# K64f_XFBGA_121_pin.net
KiCad netlist of a schematic drawn in Altium Designer
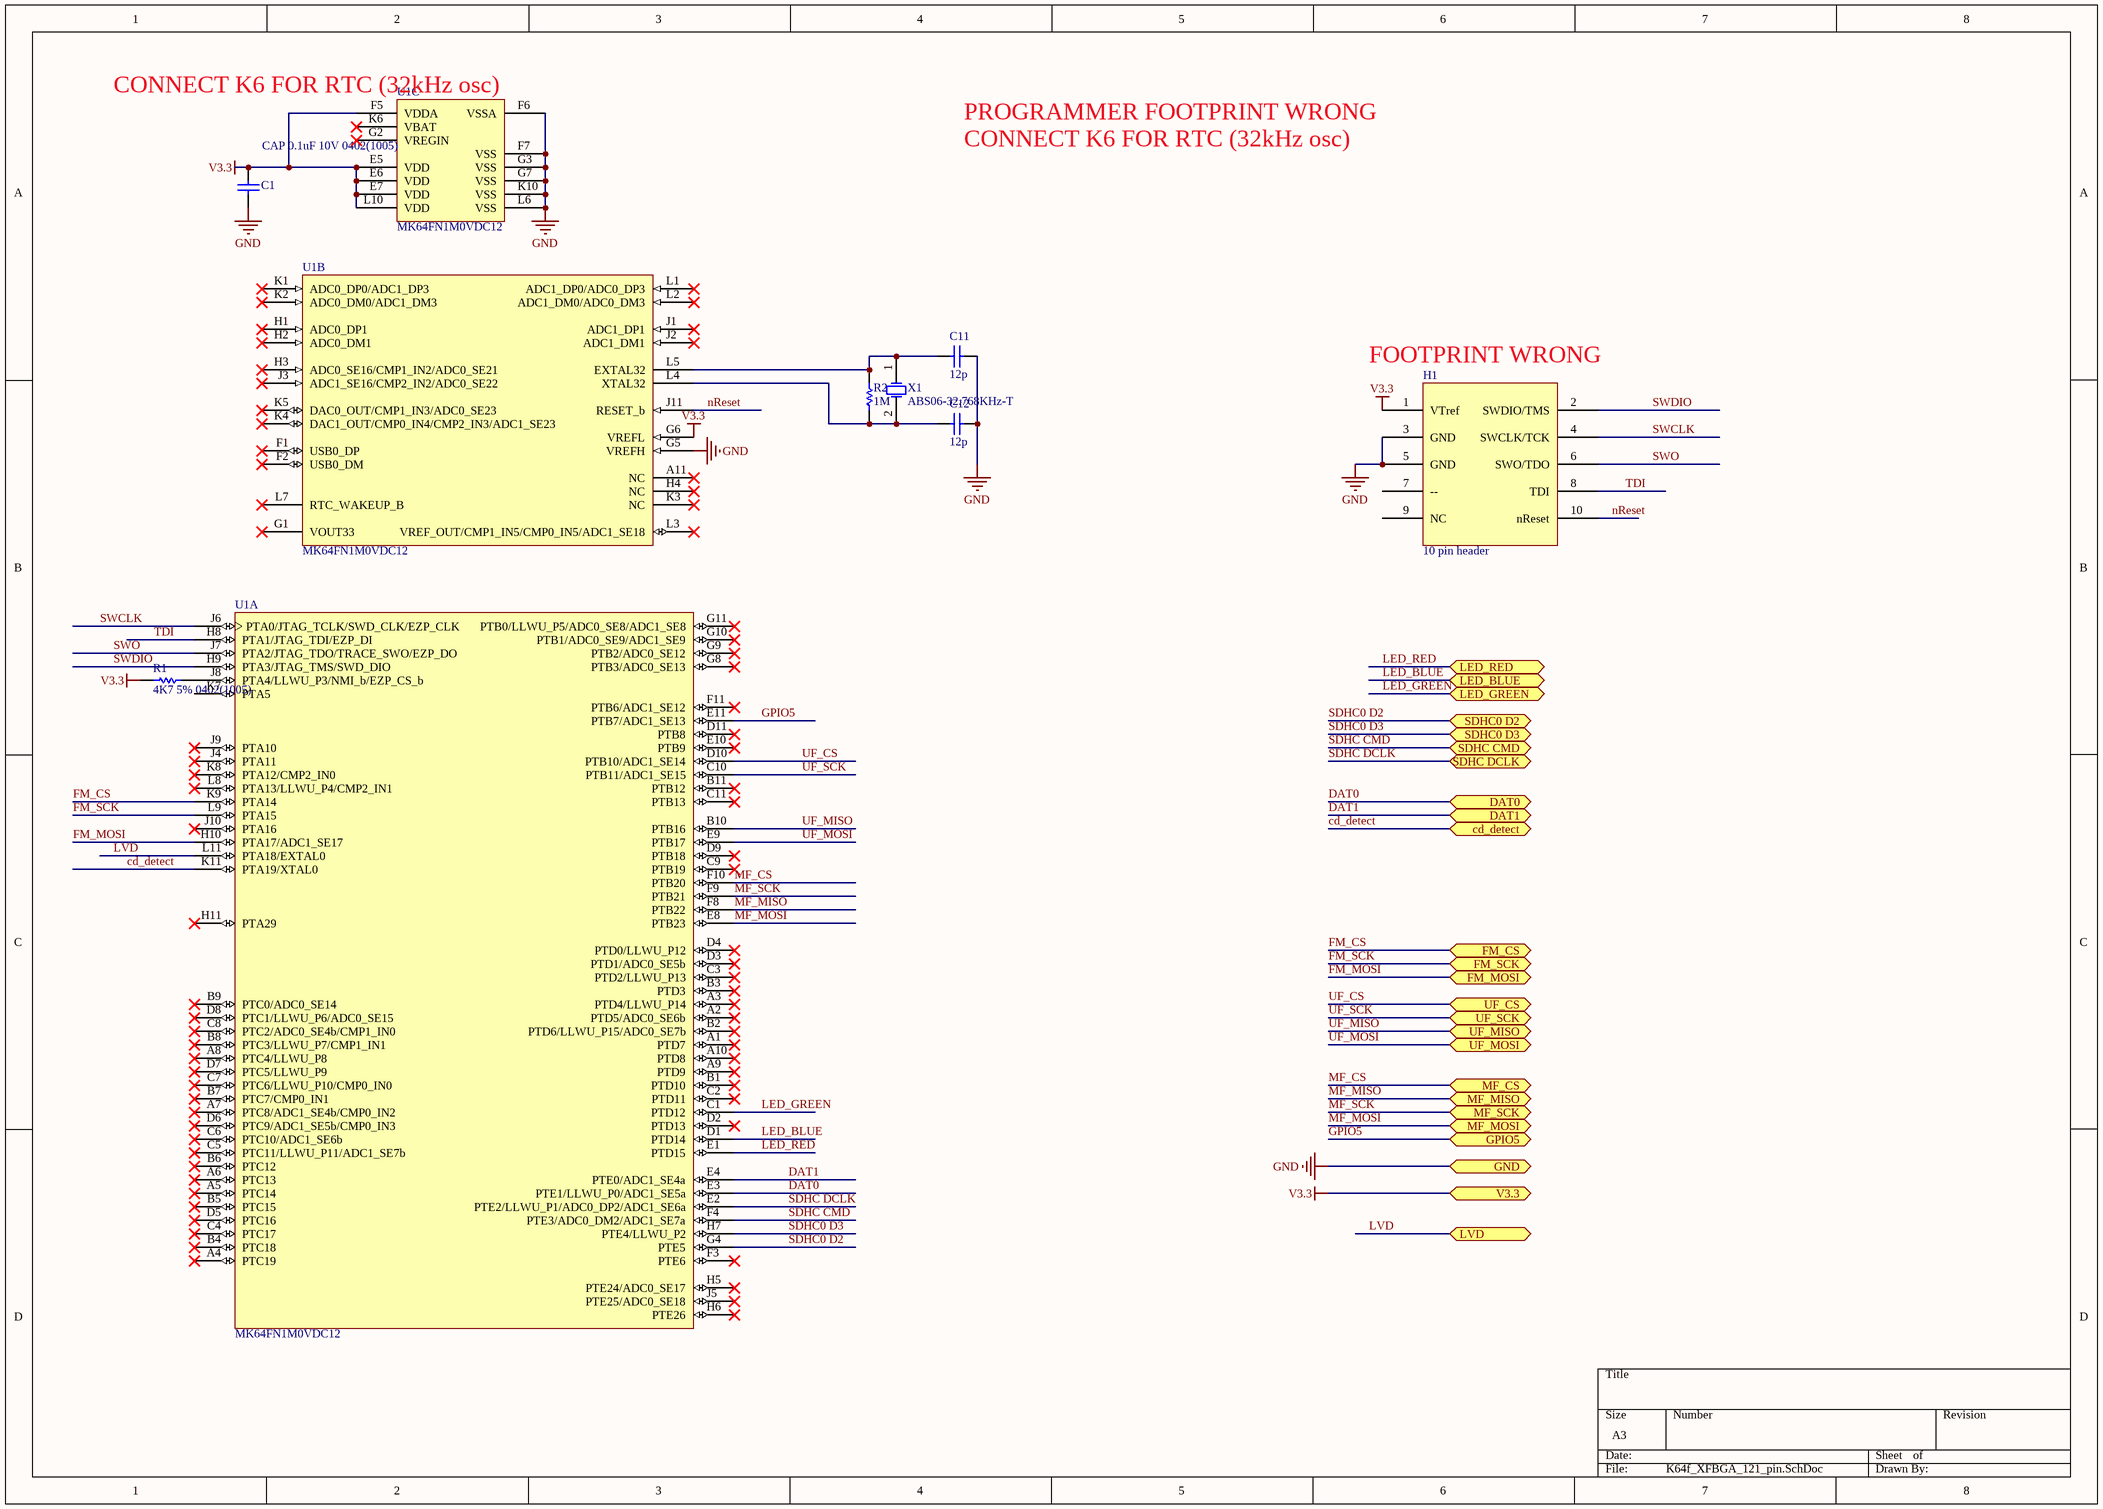
[diagram p0: K64f_XFBGA_121_pin.SchDoc]

(export (version "E")
  (design (tool "Eeschema 10.0.6"))
  (components
    (comp (ref "C1")
      (value "CAP 0.1uF 10V 0402(1005)")
      (footprint "CAPC0402(1005)60_M")
      (description "0.1uF")
      (fields (field (name "TOLERANCE") "Â±0.1pF"))
      (libsource (lib "Altium Content Vault") (part "CAP"))
    )
    (comp (ref "C11")
      (value "12p")
      (footprint "CAPC0402(1005)60_M")
      (description "CAP 12pF 10V ±0.1pF 0402 (1005 Metric) Thickness 0.6mm SMD")
      (fields (field (name "TOLERANCE") "Â±0.1pF"))
      (libsource (lib "Altium Content Vault") (part "CMP-1034-00013-1"))
    )
    (comp (ref "C12")
      (value "12p")
      (footprint "CAPC0402(1005)60_M")
      (description "CAP 12pF 10V ±0.1pF 0402 (1005 Metric) Thickness 0.6mm SMD")
      (fields (field (name "TOLERANCE") "Â±0.1pF"))
      (libsource (lib "Altium Content Vault") (part "CMP-1034-00013-1"))
    )
    (comp (ref "H1")
      (value "10 pin header")
      (footprint "SAM8795-ND")
      (description "10 pin programming header SAM8795-ND")
      (libsource (lib "Senseback_lib") (part "SAM8795-ND"))
    )
    (comp (ref "R1")
      (value "4K7 5% 0402(1005)")
      (footprint "RESC0402(1005)_L")
      (description "4K7 0.063W 5% 0402 (1005 Metric)  SMD")
      (fields (field (name "TOLERANCE") "5 %") (field (name "POWER") "0.063 W"))
      (libsource (lib "Altium Content Vault") (part "RES"))
    )
    (comp (ref "R2")
      (value "1M")
      (footprint "RESC0402(1005)_L")
      (description "1M 0.063W 5% 0402 (1005 Metric)  SMD")
      (fields (field (name "TOLERANCE") "5 %") (field (name "POWER") "0.063 W"))
      (libsource (lib "Altium Content Vault") (part "CMP-1011-00090-1"))
    )
    (comp (ref "U1")
      (value "MK64FN1M0VDC12")
      (footprint "FRES-MAPBGA-121")
      (fields (field (name "MANUFACTURER") "Freescale Semiconductor"))
      (libsource (lib "Altium Content Vault") (part "FRES-MK64FX512VDC12-121"))
    )
    (comp (ref "X1")
      (value "ABS06-32.768KHz-T")
      (footprint "0805")
      (description "Crystals 32.768KHz 20ppm 12.5pF -40C +85C 0805(2012)")
      (fields (field (name "PARTNUMBER") "14340272-32.768KHz") (field (name "MANUFACTURER") "ITTI"))
      (libsource (lib "altium-import") (part "root_3_ITTI-14340272-2_"))
    )
  )
  (nets
    (net (code "1") (name "/DAT0") (class "Default")
      (node (ref "U1") (pin "E3") (pinfunction "PTE1/LLWU_P0/ADC1_SE5a_E3") (pintype "bidirectional"))
    )
    (net (code "2") (name "/DAT1") (class "Default")
      (node (ref "U1") (pin "E4") (pinfunction "PTE0/ADC1_SE4a_E4") (pintype "bidirectional"))
    )
    (net (code "3") (name "/FM_CS") (class "Default")
      (node (ref "U1") (pin "K9") (pinfunction "PTA14_K9") (pintype "bidirectional"))
    )
    (net (code "4") (name "/FM_MOSI") (class "Default")
      (node (ref "U1") (pin "H10") (pinfunction "PTA17/ADC1_SE17_H10") (pintype "bidirectional"))
    )
    (net (code "5") (name "/FM_SCK") (class "Default")
      (node (ref "U1") (pin "L9") (pinfunction "PTA15_L9") (pintype "bidirectional"))
    )
    (net (code "6") (name "/GPIO5") (class "Default")
      (node (ref "U1") (pin "E11") (pinfunction "PTB7/ADC1_SE13_E11") (pintype "bidirectional"))
    )
    (net (code "7") (name "/LED_BLUE") (class "Default")
      (node (ref "U1") (pin "D1") (pinfunction "PTD14_D1") (pintype "bidirectional"))
    )
    (net (code "8") (name "/LED_GREEN") (class "Default")
      (node (ref "U1") (pin "C1") (pinfunction "PTD12_C1") (pintype "bidirectional"))
    )
    (net (code "9") (name "/LED_RED") (class "Default")
      (node (ref "U1") (pin "E1") (pinfunction "PTD15_E1") (pintype "bidirectional"))
    )
    (net (code "10") (name "/LVD") (class "Default")
      (node (ref "U1") (pin "L11") (pinfunction "PTA18/EXTAL0_L11") (pintype "bidirectional"))
    )
    (net (code "11") (name "/MF_CS") (class "Default")
      (node (ref "U1") (pin "F10") (pinfunction "PTB20_F10") (pintype "bidirectional"))
    )
    (net (code "12") (name "/MF_MISO") (class "Default")
      (node (ref "U1") (pin "F8") (pinfunction "PTB22_F8") (pintype "bidirectional"))
    )
    (net (code "13") (name "/MF_MOSI") (class "Default")
      (node (ref "U1") (pin "E8") (pinfunction "PTB23_E8") (pintype "bidirectional"))
    )
    (net (code "14") (name "/MF_SCK") (class "Default")
      (node (ref "U1") (pin "F9") (pinfunction "PTB21_F9") (pintype "bidirectional"))
    )
    (net (code "15") (name "/SDHC CMD") (class "Default")
      (node (ref "U1") (pin "F4") (pinfunction "PTE3/ADC0_DM2/ADC1_SE7a_F4") (pintype "bidirectional"))
    )
    (net (code "16") (name "/SDHC DCLK") (class "Default")
      (node (ref "U1") (pin "E2") (pinfunction "PTE2/LLWU_P1/ADC0_DP2/ADC1_SE6a_E2") (pintype "bidirectional"))
    )
    (net (code "17") (name "/SDHC0 D2") (class "Default")
      (node (ref "U1") (pin "G4") (pinfunction "PTE5_G4") (pintype "bidirectional"))
    )
    (net (code "18") (name "/SDHC0 D3") (class "Default")
      (node (ref "U1") (pin "H7") (pinfunction "PTE4/LLWU_P2_H7") (pintype "bidirectional"))
    )
    (net (code "19") (name "/SWCLK") (class "Default")
      (node (ref "H1") (pin "4") (pinfunction "SWCLK/TCK_4") (pintype "passive"))
      (node (ref "U1") (pin "J6") (pinfunction "PTA0/JTAG_TCLK/SWD_CLK/EZP_CLK_J6") (pintype "bidirectional"))
    )
    (net (code "20") (name "/SWDIO") (class "Default")
      (node (ref "H1") (pin "2") (pinfunction "SWDIO/TMS_2") (pintype "passive"))
      (node (ref "U1") (pin "H9") (pinfunction "PTA3/JTAG_TMS/SWD_DIO_H9") (pintype "bidirectional"))
    )
    (net (code "21") (name "/SWO") (class "Default")
      (node (ref "H1") (pin "6") (pinfunction "SWO/TDO_6") (pintype "passive"))
      (node (ref "U1") (pin "J7") (pinfunction "PTA2/JTAG_TDO/TRACE_SWO/EZP_DO_J7") (pintype "bidirectional"))
    )
    (net (code "22") (name "/TDI") (class "Default")
      (node (ref "H1") (pin "8") (pinfunction "TDI_8") (pintype "passive"))
      (node (ref "U1") (pin "H8") (pinfunction "PTA1/JTAG_TDI/EZP_DI_H8") (pintype "bidirectional"))
    )
    (net (code "23") (name "/UF_CS") (class "Default")
      (node (ref "U1") (pin "D10") (pinfunction "PTB10/ADC1_SE14_D10") (pintype "bidirectional"))
    )
    (net (code "24") (name "/UF_MISO") (class "Default")
      (node (ref "U1") (pin "B10") (pinfunction "PTB16_B10") (pintype "bidirectional"))
    )
    (net (code "25") (name "/UF_MOSI") (class "Default")
      (node (ref "U1") (pin "E9") (pinfunction "PTB17_E9") (pintype "bidirectional"))
    )
    (net (code "26") (name "/UF_SCK") (class "Default")
      (node (ref "U1") (pin "C10") (pinfunction "PTB11/ADC1_SE15_C10") (pintype "bidirectional"))
    )
    (net (code "27") (name "/cd_detect") (class "Default")
      (node (ref "U1") (pin "K11") (pinfunction "PTA19/XTAL0_K11") (pintype "bidirectional"))
    )
    (net (code "28") (name "/nReset") (class "Default")
      (node (ref "H1") (pin "10") (pinfunction "nReset_10") (pintype "passive"))
      (node (ref "U1") (pin "J11") (pinfunction "RESET_b_J11") (pintype "input"))
    )
    (net (code "29") (name "GND") (class "Default")
      (node (ref "C1") (pin "1") (pinfunction "1_1") (pintype "passive"))
      (node (ref "C11") (pin "1") (pinfunction "1_1") (pintype "passive"))
      (node (ref "C12") (pin "1") (pinfunction "1_1") (pintype "passive"))
      (node (ref "H1") (pin "3") (pinfunction "GND_3") (pintype "passive"))
      (node (ref "H1") (pin "5") (pinfunction "GND_5") (pintype "passive"))
      (node (ref "U1") (pin "F6") (pinfunction "VSSA_F6") (pintype "power_in"))
      (node (ref "U1") (pin "F7") (pinfunction "VSS_F7") (pintype "power_in"))
      (node (ref "U1") (pin "G3") (pinfunction "VSS_G3") (pintype "power_in"))
      (node (ref "U1") (pin "G5") (pinfunction "VREFH_G5") (pintype "input"))
      (node (ref "U1") (pin "G7") (pinfunction "VSS_G7") (pintype "power_in"))
      (node (ref "U1") (pin "K10") (pinfunction "VSS_K10") (pintype "power_in"))
      (node (ref "U1") (pin "L6") (pinfunction "VSS_L6") (pintype "power_in"))
    )
    (net (code "30") (name "Net-(U1A-PTA4{slash}LLWU_P3{slash}NMI_b{slash}EZP_CS_b)") (class "Default")
      (node (ref "R1") (pin "2") (pinfunction "2_2") (pintype "passive"))
      (node (ref "U1") (pin "J8") (pinfunction "PTA4/LLWU_P3/NMI_b/EZP_CS_b_J8") (pintype "bidirectional"))
    )
    (net (code "31") (name "Net-(U1B-EXTAL32)") (class "Default")
      (node (ref "C11") (pin "2") (pinfunction "2_2") (pintype "passive"))
      (node (ref "R2") (pin "1") (pinfunction "1_1") (pintype "passive"))
      (node (ref "U1") (pin "L5") (pinfunction "EXTAL32_L5") (pintype "passive"))
      (node (ref "X1") (pin "1") (pinfunction "X1_1") (pintype "passive"))
    )
    (net (code "32") (name "Net-(U1B-XTAL32)") (class "Default")
      (node (ref "C12") (pin "2") (pinfunction "2_2") (pintype "passive"))
      (node (ref "R2") (pin "2") (pinfunction "2_2") (pintype "passive"))
      (node (ref "U1") (pin "L4") (pinfunction "XTAL32_L4") (pintype "passive"))
      (node (ref "X1") (pin "2") (pinfunction "X2_2") (pintype "passive"))
    )
    (net (code "33") (name "V3.3") (class "Default")
      (node (ref "C1") (pin "2") (pinfunction "2_2") (pintype "passive"))
      (node (ref "H1") (pin "1") (pinfunction "VTref_1") (pintype "passive"))
      (node (ref "R1") (pin "1") (pinfunction "1_1") (pintype "passive"))
      (node (ref "U1") (pin "E5") (pinfunction "VDD_E5") (pintype "power_in"))
      (node (ref "U1") (pin "E6") (pinfunction "VDD_E6") (pintype "power_in"))
      (node (ref "U1") (pin "E7") (pinfunction "VDD_E7") (pintype "power_in"))
      (node (ref "U1") (pin "F5") (pinfunction "VDDA_F5") (pintype "power_in"))
      (node (ref "U1") (pin "G6") (pinfunction "VREFL_G6") (pintype "input"))
      (node (ref "U1") (pin "L10") (pinfunction "VDD_L10") (pintype "power_in"))
    )
    (net (code "34") (name "unconnected-(H1----Pad7)") (class "Default")
      (node (ref "H1") (pin "7") (pinfunction "--_7") (pintype "passive"))
    )
    (net (code "35") (name "unconnected-(H1-NC-Pad9)") (class "Default")
      (node (ref "H1") (pin "9") (pinfunction "NC_9") (pintype "passive"))
    )
    (net (code "36") (name "unconnected-(U1A-PTA5-PadK7)") (class "Default")
      (node (ref "U1") (pin "K7") (pinfunction "PTA5_K7") (pintype "bidirectional"))
    )
    (net (code "37") (name "unconnected-(U1A-PTA10-PadJ9)") (class "Default")
      (node (ref "U1") (pin "J9") (pinfunction "PTA10_J9") (pintype "bidirectional+no_connect"))
    )
    (net (code "38") (name "unconnected-(U1A-PTA11-PadJ4)") (class "Default")
      (node (ref "U1") (pin "J4") (pinfunction "PTA11_J4") (pintype "bidirectional+no_connect"))
    )
    (net (code "39") (name "unconnected-(U1A-PTA12{slash}CMP2_IN0-PadK8)") (class "Default")
      (node (ref "U1") (pin "K8") (pinfunction "PTA12/CMP2_IN0_K8") (pintype "bidirectional+no_connect"))
    )
    (net (code "40") (name "unconnected-(U1A-PTA13{slash}LLWU_P4{slash}CMP2_IN1-PadL8)") (class "Default")
      (node (ref "U1") (pin "L8") (pinfunction "PTA13/LLWU_P4/CMP2_IN1_L8") (pintype "bidirectional+no_connect"))
    )
    (net (code "41") (name "unconnected-(U1A-PTA16-PadJ10)") (class "Default")
      (node (ref "U1") (pin "J10") (pinfunction "PTA16_J10") (pintype "bidirectional+no_connect"))
    )
    (net (code "42") (name "unconnected-(U1A-PTA29-PadH11)") (class "Default")
      (node (ref "U1") (pin "H11") (pinfunction "PTA29_H11") (pintype "bidirectional+no_connect"))
    )
    (net (code "43") (name "unconnected-(U1A-PTB0{slash}LLWU_P5{slash}ADC0_SE8{slash}ADC1_SE8-PadG11)") (class "Default")
      (node (ref "U1") (pin "G11") (pinfunction "PTB0/LLWU_P5/ADC0_SE8/ADC1_SE8_G11") (pintype "bidirectional+no_connect"))
    )
    (net (code "44") (name "unconnected-(U1A-PTB1{slash}ADC0_SE9{slash}ADC1_SE9-PadG10)") (class "Default")
      (node (ref "U1") (pin "G10") (pinfunction "PTB1/ADC0_SE9/ADC1_SE9_G10") (pintype "bidirectional+no_connect"))
    )
    (net (code "45") (name "unconnected-(U1A-PTB2{slash}ADC0_SE12-PadG9)") (class "Default")
      (node (ref "U1") (pin "G9") (pinfunction "PTB2/ADC0_SE12_G9") (pintype "bidirectional+no_connect"))
    )
    (net (code "46") (name "unconnected-(U1A-PTB3{slash}ADC0_SE13-PadG8)") (class "Default")
      (node (ref "U1") (pin "G8") (pinfunction "PTB3/ADC0_SE13_G8") (pintype "bidirectional+no_connect"))
    )
    (net (code "47") (name "unconnected-(U1A-PTB6{slash}ADC1_SE12-PadF11)") (class "Default")
      (node (ref "U1") (pin "F11") (pinfunction "PTB6/ADC1_SE12_F11") (pintype "bidirectional+no_connect"))
    )
    (net (code "48") (name "unconnected-(U1A-PTB8-PadD11)") (class "Default")
      (node (ref "U1") (pin "D11") (pinfunction "PTB8_D11") (pintype "bidirectional+no_connect"))
    )
    (net (code "49") (name "unconnected-(U1A-PTB9-PadE10)") (class "Default")
      (node (ref "U1") (pin "E10") (pinfunction "PTB9_E10") (pintype "bidirectional+no_connect"))
    )
    (net (code "50") (name "unconnected-(U1A-PTB12-PadB11)") (class "Default")
      (node (ref "U1") (pin "B11") (pinfunction "PTB12_B11") (pintype "bidirectional+no_connect"))
    )
    (net (code "51") (name "unconnected-(U1A-PTB13-PadC11)") (class "Default")
      (node (ref "U1") (pin "C11") (pinfunction "PTB13_C11") (pintype "bidirectional+no_connect"))
    )
    (net (code "52") (name "unconnected-(U1A-PTB18-PadD9)") (class "Default")
      (node (ref "U1") (pin "D9") (pinfunction "PTB18_D9") (pintype "bidirectional+no_connect"))
    )
    (net (code "53") (name "unconnected-(U1A-PTB19-PadC9)") (class "Default")
      (node (ref "U1") (pin "C9") (pinfunction "PTB19_C9") (pintype "bidirectional+no_connect"))
    )
    (net (code "54") (name "unconnected-(U1A-PTC0{slash}ADC0_SE14-PadB9)") (class "Default")
      (node (ref "U1") (pin "B9") (pinfunction "PTC0/ADC0_SE14_B9") (pintype "bidirectional+no_connect"))
    )
    (net (code "55") (name "unconnected-(U1A-PTC1{slash}LLWU_P6{slash}ADC0_SE15-PadD8)") (class "Default")
      (node (ref "U1") (pin "D8") (pinfunction "PTC1/LLWU_P6/ADC0_SE15_D8") (pintype "bidirectional+no_connect"))
    )
    (net (code "56") (name "unconnected-(U1A-PTC2{slash}ADC0_SE4b{slash}CMP1_IN0-PadC8)") (class "Default")
      (node (ref "U1") (pin "C8") (pinfunction "PTC2/ADC0_SE4b/CMP1_IN0_C8") (pintype "bidirectional+no_connect"))
    )
    (net (code "57") (name "unconnected-(U1A-PTC3{slash}LLWU_P7{slash}CMP1_IN1-PadB8)") (class "Default")
      (node (ref "U1") (pin "B8") (pinfunction "PTC3/LLWU_P7/CMP1_IN1_B8") (pintype "bidirectional+no_connect"))
    )
    (net (code "58") (name "unconnected-(U1A-PTC4{slash}LLWU_P8-PadA8)") (class "Default")
      (node (ref "U1") (pin "A8") (pinfunction "PTC4/LLWU_P8_A8") (pintype "bidirectional+no_connect"))
    )
    (net (code "59") (name "unconnected-(U1A-PTC5{slash}LLWU_P9-PadD7)") (class "Default")
      (node (ref "U1") (pin "D7") (pinfunction "PTC5/LLWU_P9_D7") (pintype "bidirectional+no_connect"))
    )
    (net (code "60") (name "unconnected-(U1A-PTC6{slash}LLWU_P10{slash}CMP0_IN0-PadC7)") (class "Default")
      (node (ref "U1") (pin "C7") (pinfunction "PTC6/LLWU_P10/CMP0_IN0_C7") (pintype "bidirectional+no_connect"))
    )
    (net (code "61") (name "unconnected-(U1A-PTC7{slash}CMP0_IN1-PadB7)") (class "Default")
      (node (ref "U1") (pin "B7") (pinfunction "PTC7/CMP0_IN1_B7") (pintype "bidirectional+no_connect"))
    )
    (net (code "62") (name "unconnected-(U1A-PTC8{slash}ADC1_SE4b{slash}CMP0_IN2-PadA7)") (class "Default")
      (node (ref "U1") (pin "A7") (pinfunction "PTC8/ADC1_SE4b/CMP0_IN2_A7") (pintype "bidirectional+no_connect"))
    )
    (net (code "63") (name "unconnected-(U1A-PTC9{slash}ADC1_SE5b{slash}CMP0_IN3-PadD6)") (class "Default")
      (node (ref "U1") (pin "D6") (pinfunction "PTC9/ADC1_SE5b/CMP0_IN3_D6") (pintype "bidirectional+no_connect"))
    )
    (net (code "64") (name "unconnected-(U1A-PTC10{slash}ADC1_SE6b-PadC6)") (class "Default")
      (node (ref "U1") (pin "C6") (pinfunction "PTC10/ADC1_SE6b_C6") (pintype "bidirectional+no_connect"))
    )
    (net (code "65") (name "unconnected-(U1A-PTC11{slash}LLWU_P11{slash}ADC1_SE7b-PadC5)") (class "Default")
      (node (ref "U1") (pin "C5") (pinfunction "PTC11/LLWU_P11/ADC1_SE7b_C5") (pintype "bidirectional+no_connect"))
    )
    (net (code "66") (name "unconnected-(U1A-PTC12-PadB6)") (class "Default")
      (node (ref "U1") (pin "B6") (pinfunction "PTC12_B6") (pintype "bidirectional+no_connect"))
    )
    (net (code "67") (name "unconnected-(U1A-PTC13-PadA6)") (class "Default")
      (node (ref "U1") (pin "A6") (pinfunction "PTC13_A6") (pintype "bidirectional+no_connect"))
    )
    (net (code "68") (name "unconnected-(U1A-PTC14-PadA5)") (class "Default")
      (node (ref "U1") (pin "A5") (pinfunction "PTC14_A5") (pintype "bidirectional+no_connect"))
    )
    (net (code "69") (name "unconnected-(U1A-PTC15-PadB5)") (class "Default")
      (node (ref "U1") (pin "B5") (pinfunction "PTC15_B5") (pintype "bidirectional+no_connect"))
    )
    (net (code "70") (name "unconnected-(U1A-PTC16-PadD5)") (class "Default")
      (node (ref "U1") (pin "D5") (pinfunction "PTC16_D5") (pintype "bidirectional+no_connect"))
    )
    (net (code "71") (name "unconnected-(U1A-PTC17-PadC4)") (class "Default")
      (node (ref "U1") (pin "C4") (pinfunction "PTC17_C4") (pintype "bidirectional+no_connect"))
    )
    (net (code "72") (name "unconnected-(U1A-PTC18-PadB4)") (class "Default")
      (node (ref "U1") (pin "B4") (pinfunction "PTC18_B4") (pintype "bidirectional+no_connect"))
    )
    (net (code "73") (name "unconnected-(U1A-PTC19-PadA4)") (class "Default")
      (node (ref "U1") (pin "A4") (pinfunction "PTC19_A4") (pintype "bidirectional+no_connect"))
    )
    (net (code "74") (name "unconnected-(U1A-PTD0{slash}LLWU_P12-PadD4)") (class "Default")
      (node (ref "U1") (pin "D4") (pinfunction "PTD0/LLWU_P12_D4") (pintype "bidirectional+no_connect"))
    )
    (net (code "75") (name "unconnected-(U1A-PTD1{slash}ADC0_SE5b-PadD3)") (class "Default")
      (node (ref "U1") (pin "D3") (pinfunction "PTD1/ADC0_SE5b_D3") (pintype "bidirectional+no_connect"))
    )
    (net (code "76") (name "unconnected-(U1A-PTD2{slash}LLWU_P13-PadC3)") (class "Default")
      (node (ref "U1") (pin "C3") (pinfunction "PTD2/LLWU_P13_C3") (pintype "bidirectional+no_connect"))
    )
    (net (code "77") (name "unconnected-(U1A-PTD3-PadB3)") (class "Default")
      (node (ref "U1") (pin "B3") (pinfunction "PTD3_B3") (pintype "bidirectional+no_connect"))
    )
    (net (code "78") (name "unconnected-(U1A-PTD4{slash}LLWU_P14-PadA3)") (class "Default")
      (node (ref "U1") (pin "A3") (pinfunction "PTD4/LLWU_P14_A3") (pintype "bidirectional+no_connect"))
    )
    (net (code "79") (name "unconnected-(U1A-PTD5{slash}ADC0_SE6b-PadA2)") (class "Default")
      (node (ref "U1") (pin "A2") (pinfunction "PTD5/ADC0_SE6b_A2") (pintype "bidirectional+no_connect"))
    )
    (net (code "80") (name "unconnected-(U1A-PTD6{slash}LLWU_P15{slash}ADC0_SE7b-PadB2)") (class "Default")
      (node (ref "U1") (pin "B2") (pinfunction "PTD6/LLWU_P15/ADC0_SE7b_B2") (pintype "bidirectional+no_connect"))
    )
    (net (code "81") (name "unconnected-(U1A-PTD7-PadA1)") (class "Default")
      (node (ref "U1") (pin "A1") (pinfunction "PTD7_A1") (pintype "bidirectional+no_connect"))
    )
    (net (code "82") (name "unconnected-(U1A-PTD8-PadA10)") (class "Default")
      (node (ref "U1") (pin "A10") (pinfunction "PTD8_A10") (pintype "bidirectional+no_connect"))
    )
    (net (code "83") (name "unconnected-(U1A-PTD9-PadA9)") (class "Default")
      (node (ref "U1") (pin "A9") (pinfunction "PTD9_A9") (pintype "bidirectional+no_connect"))
    )
    (net (code "84") (name "unconnected-(U1A-PTD10-PadB1)") (class "Default")
      (node (ref "U1") (pin "B1") (pinfunction "PTD10_B1") (pintype "bidirectional+no_connect"))
    )
    (net (code "85") (name "unconnected-(U1A-PTD11-PadC2)") (class "Default")
      (node (ref "U1") (pin "C2") (pinfunction "PTD11_C2") (pintype "bidirectional+no_connect"))
    )
    (net (code "86") (name "unconnected-(U1A-PTD13-PadD2)") (class "Default")
      (node (ref "U1") (pin "D2") (pinfunction "PTD13_D2") (pintype "bidirectional+no_connect"))
    )
    (net (code "87") (name "unconnected-(U1A-PTE6-PadF3)") (class "Default")
      (node (ref "U1") (pin "F3") (pinfunction "PTE6_F3") (pintype "bidirectional+no_connect"))
    )
    (net (code "88") (name "unconnected-(U1A-PTE24{slash}ADC0_SE17-PadH5)") (class "Default")
      (node (ref "U1") (pin "H5") (pinfunction "PTE24/ADC0_SE17_H5") (pintype "bidirectional+no_connect"))
    )
    (net (code "89") (name "unconnected-(U1A-PTE25{slash}ADC0_SE18-PadJ5)") (class "Default")
      (node (ref "U1") (pin "J5") (pinfunction "PTE25/ADC0_SE18_J5") (pintype "bidirectional+no_connect"))
    )
    (net (code "90") (name "unconnected-(U1A-PTE26-PadH6)") (class "Default")
      (node (ref "U1") (pin "H6") (pinfunction "PTE26_H6") (pintype "bidirectional+no_connect"))
    )
    (net (code "91") (name "unconnected-(U1B-ADC0_DM0{slash}ADC1_DM3-PadK2)") (class "Default")
      (node (ref "U1") (pin "K2") (pinfunction "ADC0_DM0/ADC1_DM3_K2") (pintype "input+no_connect"))
    )
    (net (code "92") (name "unconnected-(U1B-ADC0_DM1-PadH2)") (class "Default")
      (node (ref "U1") (pin "H2") (pinfunction "ADC0_DM1_H2") (pintype "input+no_connect"))
    )
    (net (code "93") (name "unconnected-(U1B-ADC0_DP0{slash}ADC1_DP3-PadK1)") (class "Default")
      (node (ref "U1") (pin "K1") (pinfunction "ADC0_DP0/ADC1_DP3_K1") (pintype "input+no_connect"))
    )
    (net (code "94") (name "unconnected-(U1B-ADC0_DP1-PadH1)") (class "Default")
      (node (ref "U1") (pin "H1") (pinfunction "ADC0_DP1_H1") (pintype "input+no_connect"))
    )
    (net (code "95") (name "unconnected-(U1B-ADC0_SE16{slash}CMP1_IN2{slash}ADC0_SE21-PadH3)") (class "Default")
      (node (ref "U1") (pin "H3") (pinfunction "ADC0_SE16/CMP1_IN2/ADC0_SE21_H3") (pintype "input+no_connect"))
    )
    (net (code "96") (name "unconnected-(U1B-ADC1_DM0{slash}ADC0_DM3-PadL2)") (class "Default")
      (node (ref "U1") (pin "L2") (pinfunction "ADC1_DM0/ADC0_DM3_L2") (pintype "input+no_connect"))
    )
    (net (code "97") (name "unconnected-(U1B-ADC1_DM1-PadJ2)") (class "Default")
      (node (ref "U1") (pin "J2") (pinfunction "ADC1_DM1_J2") (pintype "input+no_connect"))
    )
    (net (code "98") (name "unconnected-(U1B-ADC1_DP0{slash}ADC0_DP3-PadL1)") (class "Default")
      (node (ref "U1") (pin "L1") (pinfunction "ADC1_DP0/ADC0_DP3_L1") (pintype "input+no_connect"))
    )
    (net (code "99") (name "unconnected-(U1B-ADC1_DP1-PadJ1)") (class "Default")
      (node (ref "U1") (pin "J1") (pinfunction "ADC1_DP1_J1") (pintype "input+no_connect"))
    )
    (net (code "100") (name "unconnected-(U1B-ADC1_SE16{slash}CMP2_IN2{slash}ADC0_SE22-PadJ3)") (class "Default")
      (node (ref "U1") (pin "J3") (pinfunction "ADC1_SE16/CMP2_IN2/ADC0_SE22_J3") (pintype "input+no_connect"))
    )
    (net (code "101") (name "unconnected-(U1B-DAC0_OUT{slash}CMP1_IN3{slash}ADC0_SE23-PadK5)") (class "Default")
      (node (ref "U1") (pin "K5") (pinfunction "DAC0_OUT/CMP1_IN3/ADC0_SE23_K5") (pintype "bidirectional+no_connect"))
    )
    (net (code "102") (name "unconnected-(U1B-DAC1_OUT{slash}CMP0_IN4{slash}CMP2_IN3{slash}ADC1_SE23-PadK4)") (class "Default")
      (node (ref "U1") (pin "K4") (pinfunction "DAC1_OUT/CMP0_IN4/CMP2_IN3/ADC1_SE23_K4") (pintype "bidirectional+no_connect"))
    )
    (net (code "103") (name "unconnected-(U1B-NC-PadA11)") (class "Default")
      (node (ref "U1") (pin "A11") (pinfunction "NC_A11") (pintype "passive+no_connect"))
    )
    (net (code "104") (name "unconnected-(U1B-NC-PadH4)") (class "Default")
      (node (ref "U1") (pin "H4") (pinfunction "NC_H4") (pintype "passive+no_connect"))
    )
    (net (code "105") (name "unconnected-(U1B-NC-PadK3)") (class "Default")
      (node (ref "U1") (pin "K3") (pinfunction "NC_K3") (pintype "passive+no_connect"))
    )
    (net (code "106") (name "unconnected-(U1B-RTC_WAKEUP_B-PadL7)") (class "Default")
      (node (ref "U1") (pin "L7") (pinfunction "RTC_WAKEUP_B_L7") (pintype "open_collector+no_connect"))
    )
    (net (code "107") (name "unconnected-(U1B-USB0_DM-PadF2)") (class "Default")
      (node (ref "U1") (pin "F2") (pinfunction "USB0_DM_F2") (pintype "bidirectional+no_connect"))
    )
    (net (code "108") (name "unconnected-(U1B-USB0_DP-PadF1)") (class "Default")
      (node (ref "U1") (pin "F1") (pinfunction "USB0_DP_F1") (pintype "bidirectional+no_connect"))
    )
    (net (code "109") (name "unconnected-(U1B-VOUT33-PadG1)") (class "Default")
      (node (ref "U1") (pin "G1") (pinfunction "VOUT33_G1") (pintype "power_in+no_connect"))
    )
    (net (code "110") (name "unconnected-(U1B-VREF_OUT{slash}CMP1_IN5{slash}CMP0_IN5{slash}ADC1_SE18-PadL3)") (class "Default")
      (node (ref "U1") (pin "L3") (pinfunction "VREF_OUT/CMP1_IN5/CMP0_IN5/ADC1_SE18_L3") (pintype "bidirectional+no_connect"))
    )
    (net (code "111") (name "unconnected-(U1C-VBAT-PadK6)") (class "Default")
      (node (ref "U1") (pin "K6") (pinfunction "VBAT_K6") (pintype "power_in+no_connect"))
    )
    (net (code "112") (name "unconnected-(U1C-VREGIN-PadG2)") (class "Default")
      (node (ref "U1") (pin "G2") (pinfunction "VREGIN_G2") (pintype "power_in+no_connect"))
    )
  )
)
